# Filters.net
KiCad netlist of a schematic drawn in Altium Designer
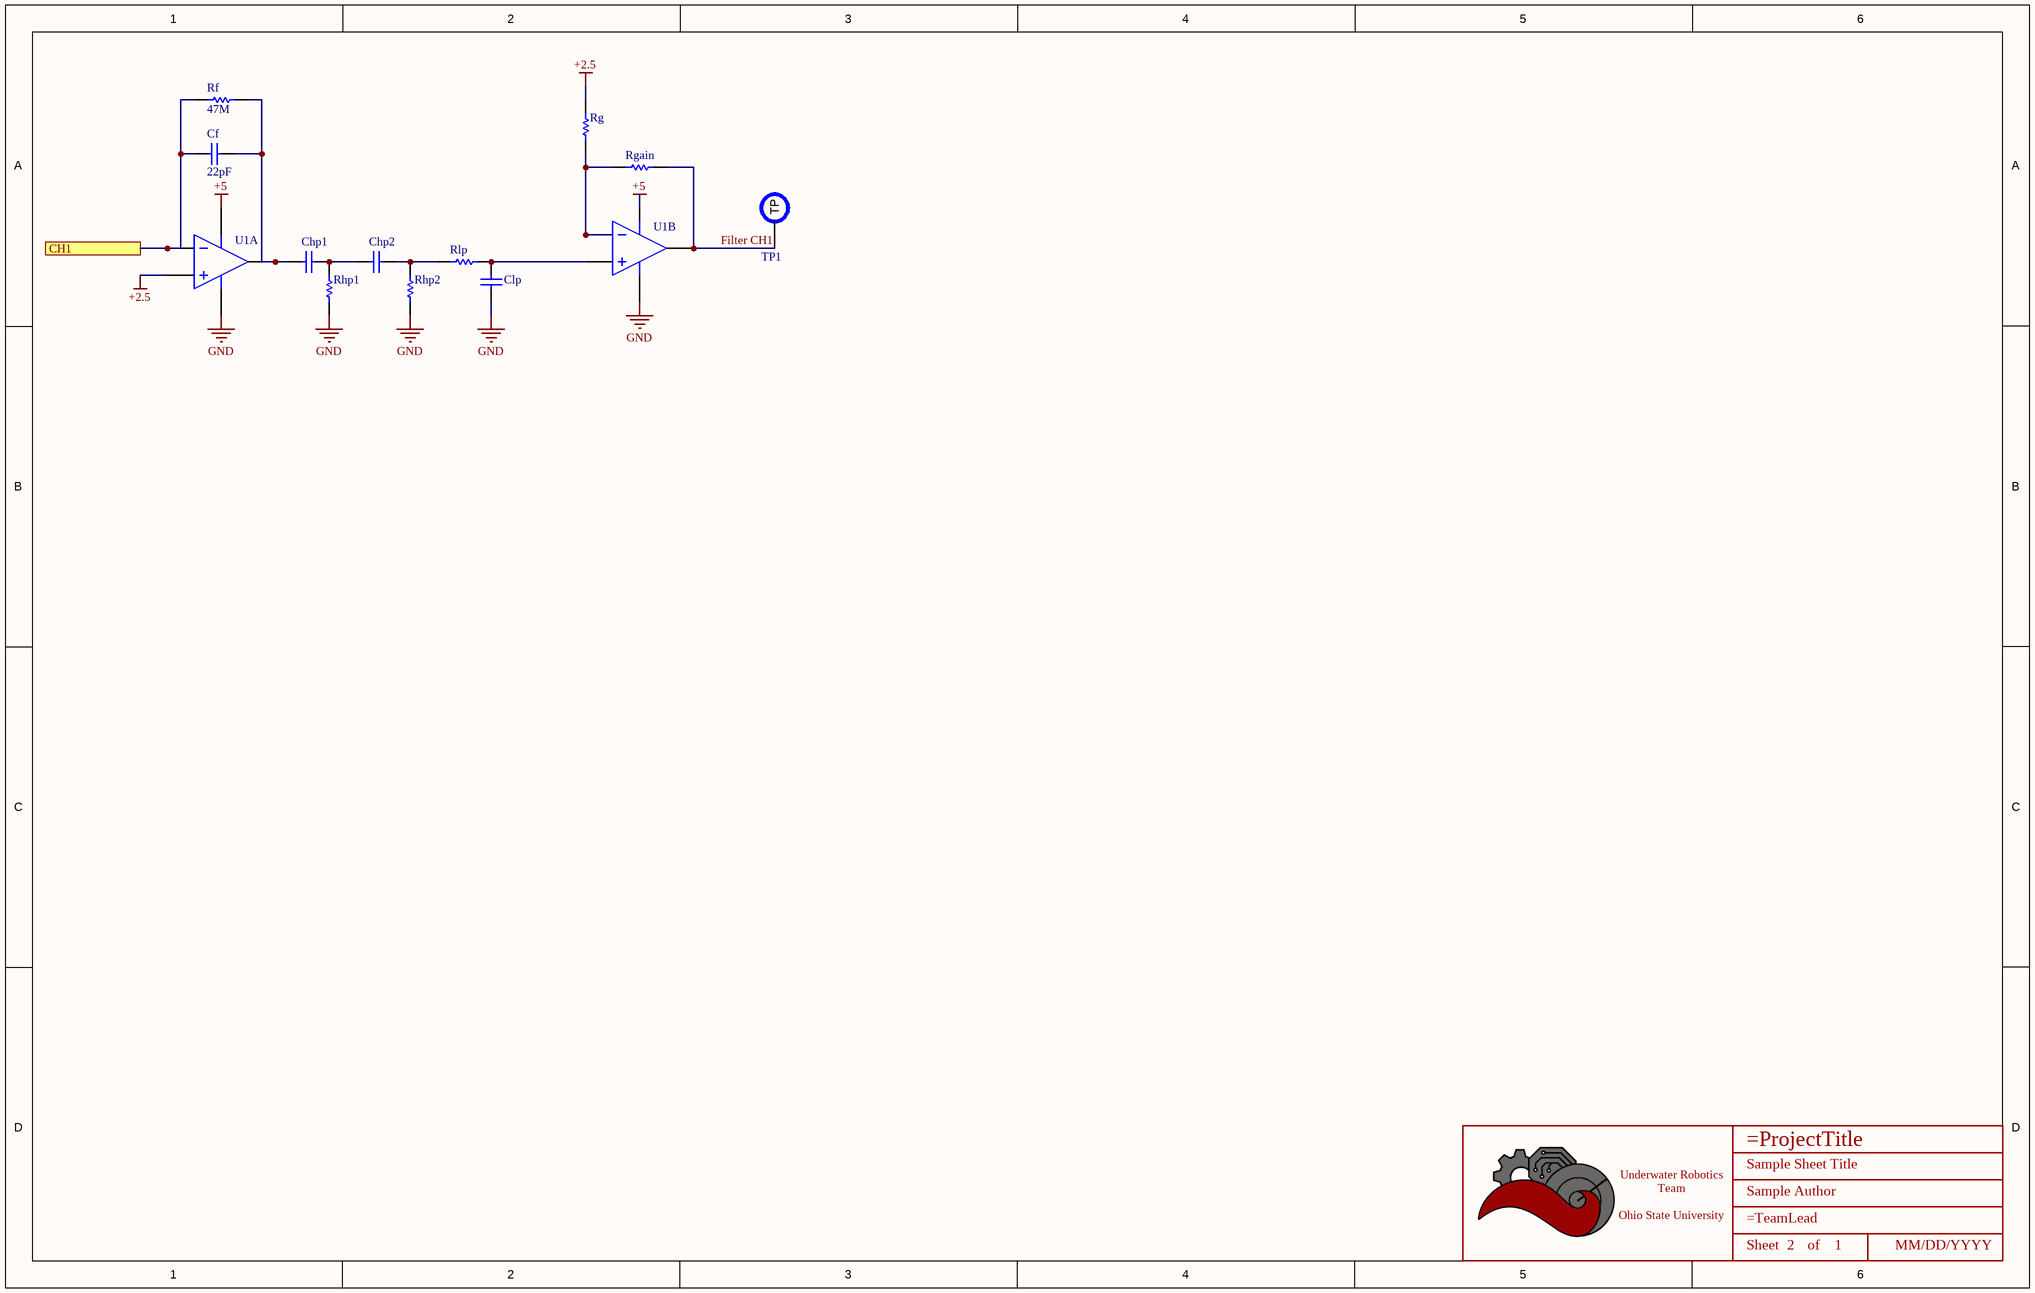
[diagram p0: Filters.SchDoc]

(export (version "E")
  (design (tool "Eeschema 10.0.6"))
  (components
    (comp (ref "*")
      (value "Title_Block")
      (footprint "LOGO")
      (description "UWRT Schematic Title Block Template\r\n\r\nCreated June 2021, Dylan Trainor")
      (libsource (lib "UWRT") (part "Title_Block"))
    )
    (comp (ref "Cf")
      (value "22pF")
      (description "Capacitor")
      (libsource (lib "Simulation Generic Components") (part "Capacitor"))
    )
    (comp (ref "Chp1")
      (value "Capacitor")
      (libsource (lib "Simulation Generic Components") (part "Capacitor"))
    )
    (comp (ref "Chp2")
      (value "Capacitor")
      (libsource (lib "Simulation Generic Components") (part "Capacitor"))
    )
    (comp (ref "Clp")
      (value "Capacitor")
      (libsource (lib "Simulation Generic Components") (part "Capacitor"))
    )
    (comp (ref "Rf")
      (value "47M")
      (description "Resistor")
      (libsource (lib "Simulation Generic Components") (part "Resistor"))
    )
    (comp (ref "Rg") (value "Resistor") (libsource (lib "Simulation Generic Components") (part "Resistor")))
    (comp (ref "Rgain")
      (value "Resistor")
      (libsource (lib "Simulation Generic Components") (part "Resistor"))
    )
    (comp (ref "Rhp1") (value "Resistor") (libsource (lib "Simulation Generic Components") (part "Resistor")))
    (comp (ref "Rhp2") (value "Resistor") (libsource (lib "Simulation Generic Components") (part "Resistor")))
    (comp (ref "Rlp") (value "Resistor") (libsource (lib "Simulation Generic Components") (part "Resistor")))
    (comp (ref "TP1")
      (value "PCB Test Point")
      (footprint "TESTPOINT_1.2MM")
      (fields (field (name "MADE BY") "Robert Pafford"))
      (libsource (lib "Connectors") (part "TESTPOINT"))
    )
    (comp (ref "U1A")
      (value "Ideal Operational Amplifier")
      (libsource (lib "Simulation Generic Components") (part "OpAmp with power terminals"))
    )
    (comp (ref "U1B")
      (value "Ideal Operational Amplifier")
      (libsource (lib "Simulation Generic Components") (part "OpAmp with power terminals"))
    )
  )
  (nets
    (net (code "1") (name "+2.5") (class "Default")
      (node (ref "Rg") (pin "2") (pinfunction "2_2") (pintype "passive"))
      (node (ref "U1A") (pin "2") (pinfunction "IN+_2") (pintype "passive"))
    )
    (net (code "2") (name "+5") (class "Default")
      (node (ref "U1A") (pin "4") (pinfunction "V+_4") (pintype "power_in"))
      (node (ref "U1B") (pin "4") (pinfunction "V+_4") (pintype "power_in"))
    )
    (net (code "3") (name "/CH1") (class "Default")
      (node (ref "Cf") (pin "1") (pinfunction "1_1") (pintype "passive"))
      (node (ref "Rf") (pin "1") (pinfunction "1_1") (pintype "passive"))
      (node (ref "U1A") (pin "1") (pinfunction "IN-_1") (pintype "passive"))
    )
    (net (code "4") (name "/Filter CH1") (class "Default")
      (node (ref "Rgain") (pin "2") (pinfunction "2_2") (pintype "passive"))
      (node (ref "TP1") (pin "TP") (pinfunction "TP_TP") (pintype "passive"))
      (node (ref "U1B") (pin "3") (pinfunction "OUT_3") (pintype "passive"))
    )
    (net (code "5") (name "GND") (class "Default")
      (node (ref "Clp") (pin "1") (pinfunction "1_1") (pintype "passive"))
      (node (ref "Rhp1") (pin "2") (pinfunction "2_2") (pintype "passive"))
      (node (ref "Rhp2") (pin "2") (pinfunction "2_2") (pintype "passive"))
      (node (ref "U1A") (pin "5") (pinfunction "V-_5") (pintype "power_in"))
      (node (ref "U1B") (pin "5") (pinfunction "V-_5") (pintype "power_in"))
    )
    (net (code "6") (name "Net-(Chp1-Pad2)") (class "Default")
      (node (ref "Chp1") (pin "2") (pinfunction "2_2") (pintype "passive"))
      (node (ref "Chp2") (pin "1") (pinfunction "1_1") (pintype "passive"))
      (node (ref "Rhp1") (pin "1") (pinfunction "1_1") (pintype "passive"))
    )
    (net (code "7") (name "Net-(Chp2-Pad2)") (class "Default")
      (node (ref "Chp2") (pin "2") (pinfunction "2_2") (pintype "passive"))
      (node (ref "Rhp2") (pin "1") (pinfunction "1_1") (pintype "passive"))
      (node (ref "Rlp") (pin "1") (pinfunction "1_1") (pintype "passive"))
    )
    (net (code "8") (name "Net-(U1A-OUT)") (class "Default")
      (node (ref "Cf") (pin "2") (pinfunction "2_2") (pintype "passive"))
      (node (ref "Chp1") (pin "1") (pinfunction "1_1") (pintype "passive"))
      (node (ref "Rf") (pin "2") (pinfunction "2_2") (pintype "passive"))
      (node (ref "U1A") (pin "3") (pinfunction "OUT_3") (pintype "passive"))
    )
    (net (code "9") (name "Net-(U1B-IN+)") (class "Default")
      (node (ref "Clp") (pin "2") (pinfunction "2_2") (pintype "passive"))
      (node (ref "Rlp") (pin "2") (pinfunction "2_2") (pintype "passive"))
      (node (ref "U1B") (pin "2") (pinfunction "IN+_2") (pintype "passive"))
    )
    (net (code "10") (name "Net-(U1B-IN-)") (class "Default")
      (node (ref "Rg") (pin "1") (pinfunction "1_1") (pintype "passive"))
      (node (ref "Rgain") (pin "1") (pinfunction "1_1") (pintype "passive"))
      (node (ref "U1B") (pin "1") (pinfunction "IN-_1") (pintype "passive"))
    )
  )
)
